# M640X.net
KiCad netlist of a schematic drawn in EAGLE
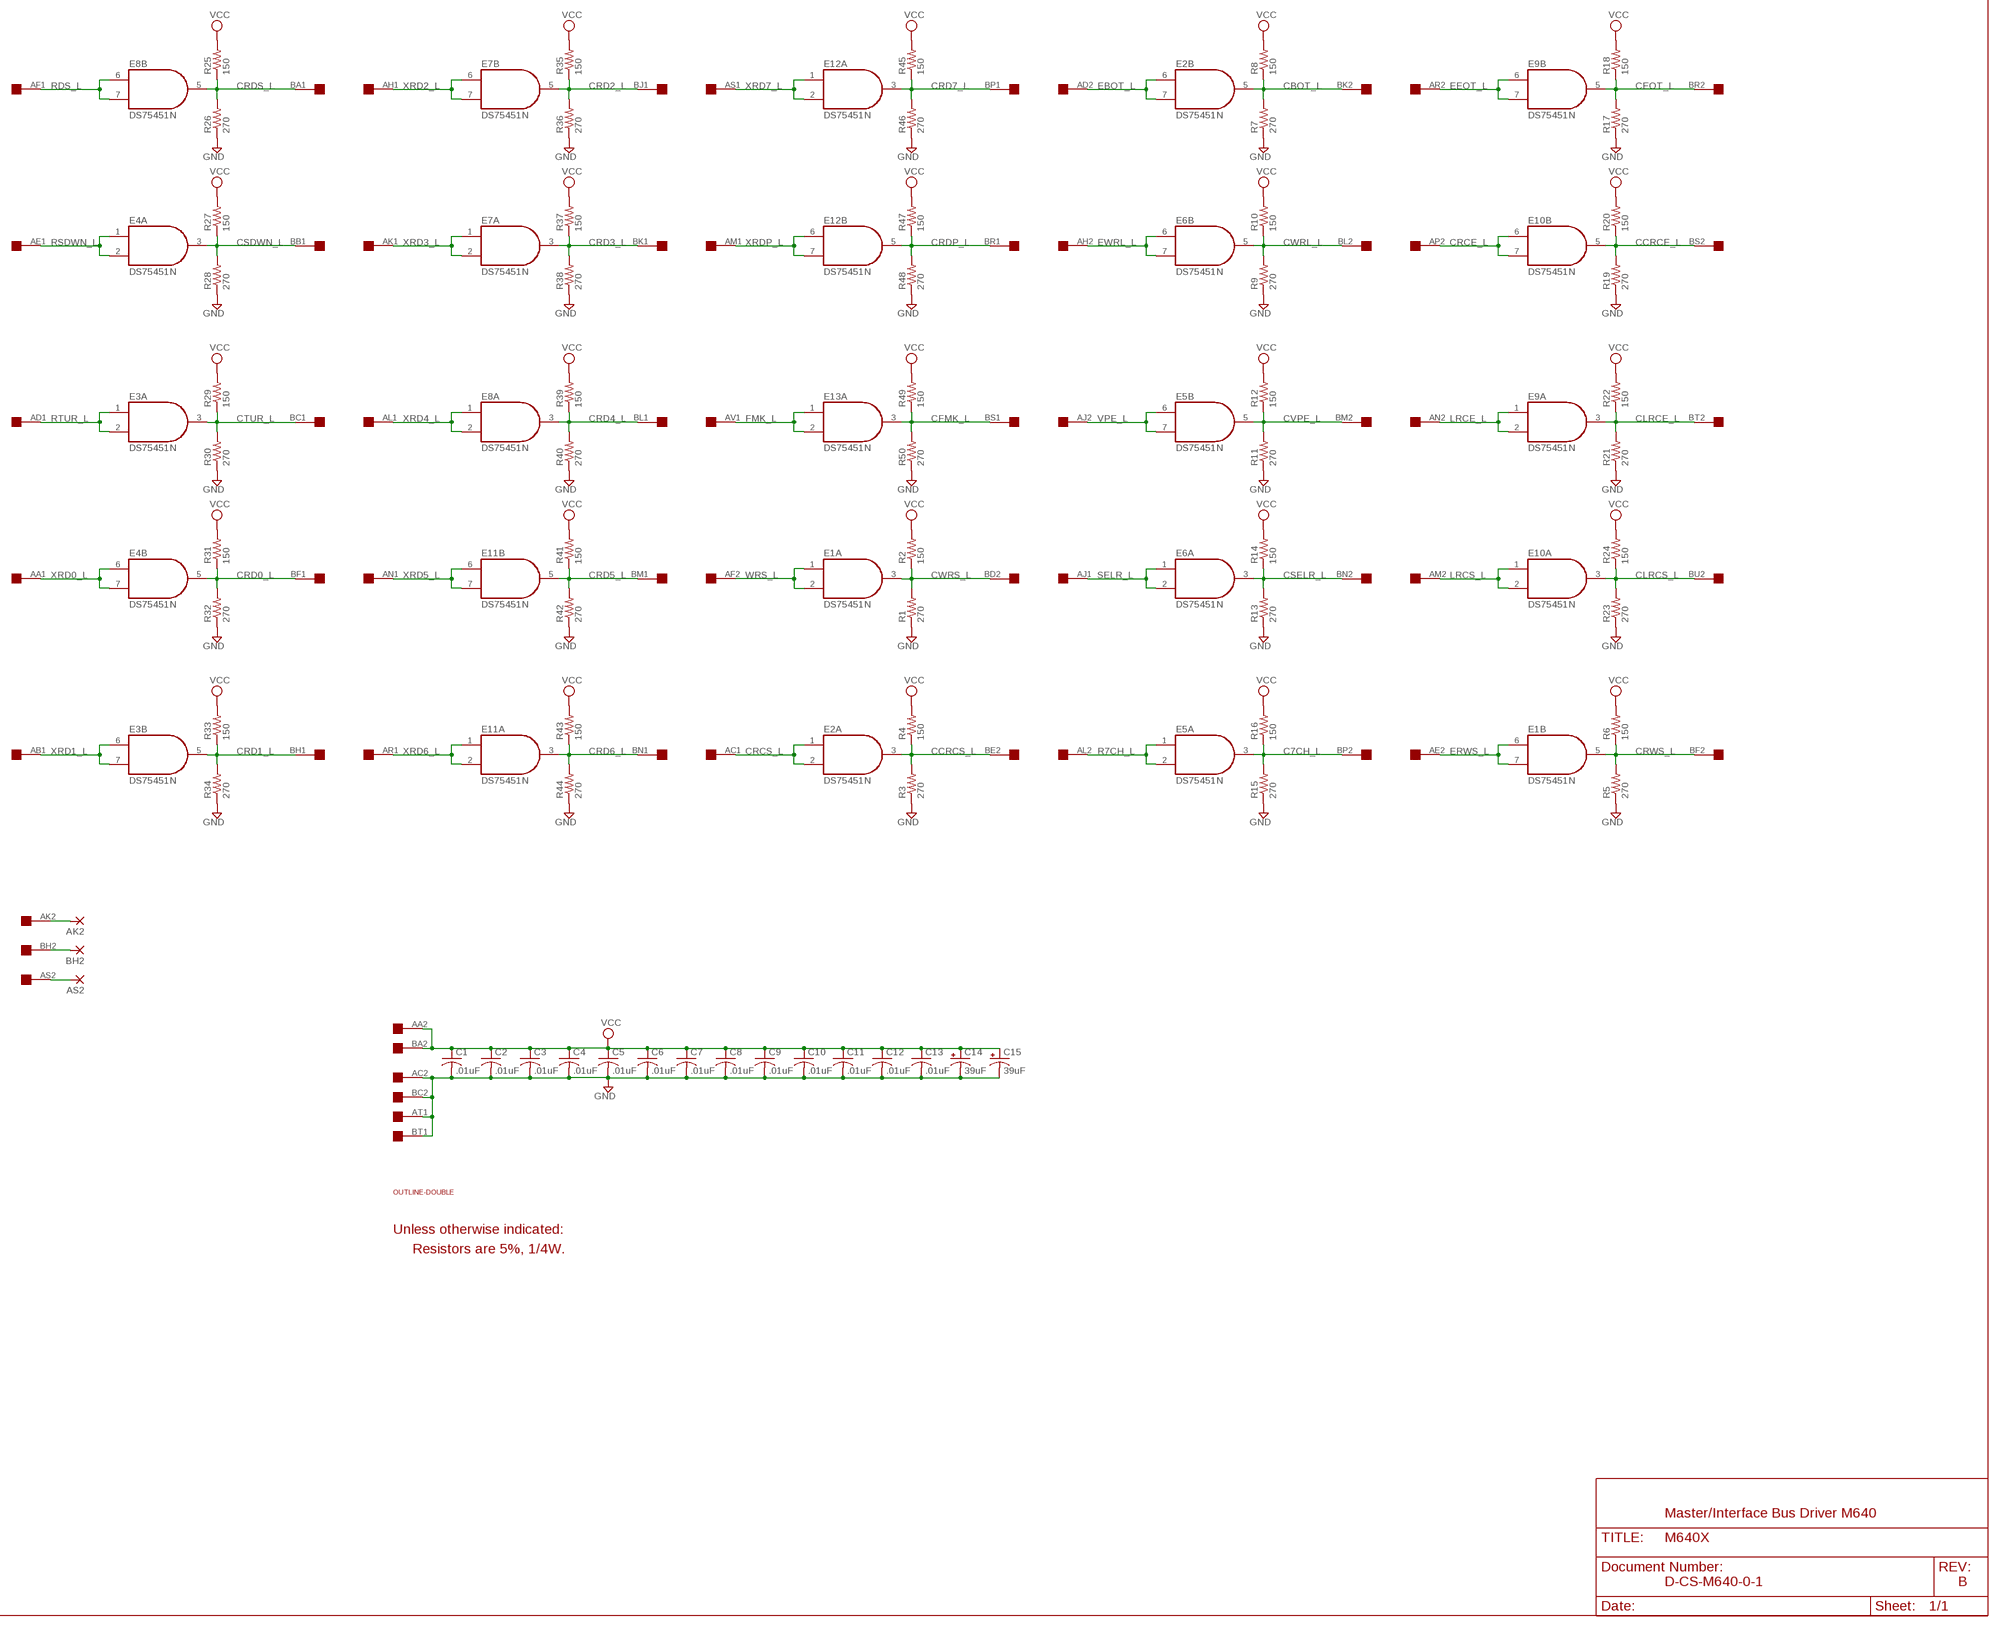
[diagram p0: schematic, sheet 1]

(export (version "E")
  (design (tool "Eeschema 10.0.6"))
  (components
    (comp (ref "AK2")
      (value "1,6/0,8")
      (footprint "eagle-import:1,6_0,8")
      (libsource (lib "eagle-import") (part "1,6/0,8"))
    )
    (comp (ref "AS2")
      (value "1,6/0,8")
      (footprint "eagle-import:1,6_0,8")
      (libsource (lib "eagle-import") (part "1,6/0,8"))
    )
    (comp (ref "BH2")
      (value "1,6/0,8")
      (footprint "eagle-import:1,6_0,8")
      (libsource (lib "eagle-import") (part "1,6/0,8"))
    )
    (comp (ref "C1")
      (value ".01uF")
      (footprint "eagle-import:C050-025X075")
      (libsource (lib "eagle-import") (part "C-US050-025X075"))
    )
    (comp (ref "C2")
      (value ".01uF")
      (footprint "eagle-import:C050-025X075")
      (libsource (lib "eagle-import") (part "C-US050-025X075"))
    )
    (comp (ref "C3")
      (value ".01uF")
      (footprint "eagle-import:C050-025X075")
      (libsource (lib "eagle-import") (part "C-US050-025X075"))
    )
    (comp (ref "C4")
      (value ".01uF")
      (footprint "eagle-import:C050-025X075")
      (libsource (lib "eagle-import") (part "C-US050-025X075"))
    )
    (comp (ref "C5")
      (value ".01uF")
      (footprint "eagle-import:C050-025X075")
      (libsource (lib "eagle-import") (part "C-US050-025X075"))
    )
    (comp (ref "C6")
      (value ".01uF")
      (footprint "eagle-import:C050-025X075")
      (libsource (lib "eagle-import") (part "C-US050-025X075"))
    )
    (comp (ref "C7")
      (value ".01uF")
      (footprint "eagle-import:C050-025X075")
      (libsource (lib "eagle-import") (part "C-US050-025X075"))
    )
    (comp (ref "C8")
      (value ".01uF")
      (footprint "eagle-import:C050-025X075")
      (libsource (lib "eagle-import") (part "C-US050-025X075"))
    )
    (comp (ref "C9")
      (value ".01uF")
      (footprint "eagle-import:C050-025X075")
      (libsource (lib "eagle-import") (part "C-US050-025X075"))
    )
    (comp (ref "C10")
      (value ".01uF")
      (footprint "eagle-import:C050-025X075")
      (libsource (lib "eagle-import") (part "C-US050-025X075"))
    )
    (comp (ref "C11")
      (value ".01uF")
      (footprint "eagle-import:C050-025X075")
      (libsource (lib "eagle-import") (part "C-US050-025X075"))
    )
    (comp (ref "C12")
      (value ".01uF")
      (footprint "eagle-import:C050-025X075")
      (libsource (lib "eagle-import") (part "C-US050-025X075"))
    )
    (comp (ref "C13")
      (value ".01uF")
      (footprint "eagle-import:C050-025X075")
      (libsource (lib "eagle-import") (part "C-US050-025X075"))
    )
    (comp (ref "C14")
      (value "39uF")
      (footprint "eagle-import:E12-8")
      (libsource (lib "eagle-import") (part "CPOL-USE20-8AXIAL"))
    )
    (comp (ref "C15")
      (value "39uF")
      (footprint "eagle-import:E12-8")
      (libsource (lib "eagle-import") (part "CPOL-USE20-8AXIAL"))
    )
    (comp (ref "E1")
      (value "DS75451N")
      (footprint "eagle-import:DIL08")
      (libsource (lib "eagle-import") (part "DS75451N"))
    )
    (comp (ref "E2")
      (value "DS75451N")
      (footprint "eagle-import:DIL08")
      (libsource (lib "eagle-import") (part "DS75451N"))
    )
    (comp (ref "E3")
      (value "DS75451N")
      (footprint "eagle-import:DIL08")
      (libsource (lib "eagle-import") (part "DS75451N"))
    )
    (comp (ref "E4")
      (value "DS75451N")
      (footprint "eagle-import:DIL08")
      (libsource (lib "eagle-import") (part "DS75451N"))
    )
    (comp (ref "E5")
      (value "DS75451N")
      (footprint "eagle-import:DIL08")
      (libsource (lib "eagle-import") (part "DS75451N"))
    )
    (comp (ref "E6")
      (value "DS75451N")
      (footprint "eagle-import:DIL08")
      (libsource (lib "eagle-import") (part "DS75451N"))
    )
    (comp (ref "E7")
      (value "DS75451N")
      (footprint "eagle-import:DIL08")
      (libsource (lib "eagle-import") (part "DS75451N"))
    )
    (comp (ref "E8")
      (value "DS75451N")
      (footprint "eagle-import:DIL08")
      (libsource (lib "eagle-import") (part "DS75451N"))
    )
    (comp (ref "E9")
      (value "DS75451N")
      (footprint "eagle-import:DIL08")
      (libsource (lib "eagle-import") (part "DS75451N"))
    )
    (comp (ref "E10")
      (value "DS75451N")
      (footprint "eagle-import:DIL08")
      (libsource (lib "eagle-import") (part "DS75451N"))
    )
    (comp (ref "E11")
      (value "DS75451N")
      (footprint "eagle-import:DIL08")
      (libsource (lib "eagle-import") (part "DS75451N"))
    )
    (comp (ref "E12")
      (value "DS75451N")
      (footprint "eagle-import:DIL08")
      (libsource (lib "eagle-import") (part "DS75451N"))
    )
    (comp (ref "E13")
      (value "DS75451N")
      (footprint "eagle-import:DIL08")
      (libsource (lib "eagle-import") (part "DS75451N"))
    )
    (comp (ref "R1")
      (value "270")
      (footprint "eagle-import:0207_10")
      (libsource (lib "eagle-import") (part "R-US_0207/10"))
    )
    (comp (ref "R2")
      (value "150")
      (footprint "eagle-import:0207_10")
      (libsource (lib "eagle-import") (part "R-US_0207/10"))
    )
    (comp (ref "R3")
      (value "270")
      (footprint "eagle-import:0207_10")
      (libsource (lib "eagle-import") (part "R-US_0207/10"))
    )
    (comp (ref "R4")
      (value "150")
      (footprint "eagle-import:0207_10")
      (libsource (lib "eagle-import") (part "R-US_0207/10"))
    )
    (comp (ref "R5")
      (value "270")
      (footprint "eagle-import:0207_10")
      (libsource (lib "eagle-import") (part "R-US_0207/10"))
    )
    (comp (ref "R6")
      (value "150")
      (footprint "eagle-import:0207_10")
      (libsource (lib "eagle-import") (part "R-US_0207/10"))
    )
    (comp (ref "R7")
      (value "270")
      (footprint "eagle-import:0207_10")
      (libsource (lib "eagle-import") (part "R-US_0207/10"))
    )
    (comp (ref "R8")
      (value "150")
      (footprint "eagle-import:0207_10")
      (libsource (lib "eagle-import") (part "R-US_0207/10"))
    )
    (comp (ref "R9")
      (value "270")
      (footprint "eagle-import:0207_10")
      (libsource (lib "eagle-import") (part "R-US_0207/10"))
    )
    (comp (ref "R10")
      (value "150")
      (footprint "eagle-import:0207_10")
      (libsource (lib "eagle-import") (part "R-US_0207/10"))
    )
    (comp (ref "R11")
      (value "270")
      (footprint "eagle-import:0207_10")
      (libsource (lib "eagle-import") (part "R-US_0207/10"))
    )
    (comp (ref "R12")
      (value "150")
      (footprint "eagle-import:0207_10")
      (libsource (lib "eagle-import") (part "R-US_0207/10"))
    )
    (comp (ref "R13")
      (value "270")
      (footprint "eagle-import:0207_10")
      (libsource (lib "eagle-import") (part "R-US_0207/10"))
    )
    (comp (ref "R14")
      (value "150")
      (footprint "eagle-import:0207_10")
      (libsource (lib "eagle-import") (part "R-US_0207/10"))
    )
    (comp (ref "R15")
      (value "270")
      (footprint "eagle-import:0207_10")
      (libsource (lib "eagle-import") (part "R-US_0207/10"))
    )
    (comp (ref "R16")
      (value "150")
      (footprint "eagle-import:0207_10")
      (libsource (lib "eagle-import") (part "R-US_0207/10"))
    )
    (comp (ref "R17")
      (value "270")
      (footprint "eagle-import:0207_10")
      (libsource (lib "eagle-import") (part "R-US_0207/10"))
    )
    (comp (ref "R18")
      (value "150")
      (footprint "eagle-import:0207_10")
      (libsource (lib "eagle-import") (part "R-US_0207/10"))
    )
    (comp (ref "R19")
      (value "270")
      (footprint "eagle-import:0207_10")
      (libsource (lib "eagle-import") (part "R-US_0207/10"))
    )
    (comp (ref "R20")
      (value "150")
      (footprint "eagle-import:0207_10")
      (libsource (lib "eagle-import") (part "R-US_0207/10"))
    )
    (comp (ref "R21")
      (value "270")
      (footprint "eagle-import:0207_10")
      (libsource (lib "eagle-import") (part "R-US_0207/10"))
    )
    (comp (ref "R22")
      (value "150")
      (footprint "eagle-import:0207_10")
      (libsource (lib "eagle-import") (part "R-US_0207/10"))
    )
    (comp (ref "R23")
      (value "270")
      (footprint "eagle-import:0207_10")
      (libsource (lib "eagle-import") (part "R-US_0207/10"))
    )
    (comp (ref "R24")
      (value "150")
      (footprint "eagle-import:0207_10")
      (libsource (lib "eagle-import") (part "R-US_0207/10"))
    )
    (comp (ref "R25")
      (value "150")
      (footprint "eagle-import:0207_10")
      (libsource (lib "eagle-import") (part "R-US_0207/10"))
    )
    (comp (ref "R26")
      (value "270")
      (footprint "eagle-import:0207_10")
      (libsource (lib "eagle-import") (part "R-US_0207/10"))
    )
    (comp (ref "R27")
      (value "150")
      (footprint "eagle-import:0207_10")
      (libsource (lib "eagle-import") (part "R-US_0207/10"))
    )
    (comp (ref "R28")
      (value "270")
      (footprint "eagle-import:0207_10")
      (libsource (lib "eagle-import") (part "R-US_0207/10"))
    )
    (comp (ref "R29")
      (value "150")
      (footprint "eagle-import:0207_10")
      (libsource (lib "eagle-import") (part "R-US_0207/10"))
    )
    (comp (ref "R30")
      (value "270")
      (footprint "eagle-import:0207_10")
      (libsource (lib "eagle-import") (part "R-US_0207/10"))
    )
    (comp (ref "R31")
      (value "150")
      (footprint "eagle-import:0207_10")
      (libsource (lib "eagle-import") (part "R-US_0207/10"))
    )
    (comp (ref "R32")
      (value "270")
      (footprint "eagle-import:0207_10")
      (libsource (lib "eagle-import") (part "R-US_0207/10"))
    )
    (comp (ref "R33")
      (value "150")
      (footprint "eagle-import:0207_10")
      (libsource (lib "eagle-import") (part "R-US_0207/10"))
    )
    (comp (ref "R34")
      (value "270")
      (footprint "eagle-import:0207_10")
      (libsource (lib "eagle-import") (part "R-US_0207/10"))
    )
    (comp (ref "R35")
      (value "150")
      (footprint "eagle-import:0207_10")
      (libsource (lib "eagle-import") (part "R-US_0207/10"))
    )
    (comp (ref "R36")
      (value "270")
      (footprint "eagle-import:0207_10")
      (libsource (lib "eagle-import") (part "R-US_0207/10"))
    )
    (comp (ref "R37")
      (value "150")
      (footprint "eagle-import:0207_10")
      (libsource (lib "eagle-import") (part "R-US_0207/10"))
    )
    (comp (ref "R38")
      (value "270")
      (footprint "eagle-import:0207_10")
      (libsource (lib "eagle-import") (part "R-US_0207/10"))
    )
    (comp (ref "R39")
      (value "150")
      (footprint "eagle-import:0207_10")
      (libsource (lib "eagle-import") (part "R-US_0207/10"))
    )
    (comp (ref "R40")
      (value "270")
      (footprint "eagle-import:0207_10")
      (libsource (lib "eagle-import") (part "R-US_0207/10"))
    )
    (comp (ref "R41")
      (value "150")
      (footprint "eagle-import:0207_10")
      (libsource (lib "eagle-import") (part "R-US_0207/10"))
    )
    (comp (ref "R42")
      (value "270")
      (footprint "eagle-import:0207_10")
      (libsource (lib "eagle-import") (part "R-US_0207/10"))
    )
    (comp (ref "R43")
      (value "150")
      (footprint "eagle-import:0207_10")
      (libsource (lib "eagle-import") (part "R-US_0207/10"))
    )
    (comp (ref "R44")
      (value "270")
      (footprint "eagle-import:0207_10")
      (libsource (lib "eagle-import") (part "R-US_0207/10"))
    )
    (comp (ref "R45")
      (value "150")
      (footprint "eagle-import:0207_10")
      (libsource (lib "eagle-import") (part "R-US_0207/10"))
    )
    (comp (ref "R46")
      (value "270")
      (footprint "eagle-import:0207_10")
      (libsource (lib "eagle-import") (part "R-US_0207/10"))
    )
    (comp (ref "R47")
      (value "150")
      (footprint "eagle-import:0207_10")
      (libsource (lib "eagle-import") (part "R-US_0207/10"))
    )
    (comp (ref "R48")
      (value "270")
      (footprint "eagle-import:0207_10")
      (libsource (lib "eagle-import") (part "R-US_0207/10"))
    )
    (comp (ref "R49")
      (value "150")
      (footprint "eagle-import:0207_10")
      (libsource (lib "eagle-import") (part "R-US_0207/10"))
    )
    (comp (ref "R50")
      (value "270")
      (footprint "eagle-import:0207_10")
      (libsource (lib "eagle-import") (part "R-US_0207/10"))
    )
    (comp (ref "U$1")
      (value "DOUBLE")
      (footprint "eagle-import:EDGE-CON4")
      (libsource (lib "eagle-import") (part "DOUBLE"))
    )
    (comp (ref "U$2")
      (value "OUTLINE-DOUBLE")
      (footprint "eagle-import:DOUBLE")
      (libsource (lib "eagle-import") (part "OUTLINE-DOUBLE"))
    )
  )
  (nets
    (net (code "1") (name "/C7CH_L") (class "Default")
      (node (ref "E5") (pin "3") (pinfunction "O_3") (pintype "open_collector"))
      (node (ref "R15") (pin "2") (pinfunction "2_2") (pintype "passive"))
      (node (ref "R16") (pin "1") (pinfunction "1_1") (pintype "passive"))
      (node (ref "U$1") (pin "BP2") (pinfunction "1_BP2") (pintype "bidirectional"))
    )
    (net (code "2") (name "/CBOT_L") (class "Default")
      (node (ref "E2") (pin "5") (pinfunction "O_5") (pintype "open_collector"))
      (node (ref "R7") (pin "2") (pinfunction "2_2") (pintype "passive"))
      (node (ref "R8") (pin "1") (pinfunction "1_1") (pintype "passive"))
      (node (ref "U$1") (pin "BK2") (pinfunction "1_BK2") (pintype "bidirectional"))
    )
    (net (code "3") (name "/CCRCE_L") (class "Default")
      (node (ref "E10") (pin "5") (pinfunction "O_5") (pintype "open_collector"))
      (node (ref "R19") (pin "2") (pinfunction "2_2") (pintype "passive"))
      (node (ref "R20") (pin "1") (pinfunction "1_1") (pintype "passive"))
      (node (ref "U$1") (pin "BS2") (pinfunction "1_BS2") (pintype "bidirectional"))
    )
    (net (code "4") (name "/CCRCS_L") (class "Default")
      (node (ref "E2") (pin "3") (pinfunction "O_3") (pintype "open_collector"))
      (node (ref "R3") (pin "2") (pinfunction "2_2") (pintype "passive"))
      (node (ref "R4") (pin "1") (pinfunction "1_1") (pintype "passive"))
      (node (ref "U$1") (pin "BE2") (pinfunction "1_BE2") (pintype "bidirectional"))
    )
    (net (code "5") (name "/CEOT_L") (class "Default")
      (node (ref "E9") (pin "5") (pinfunction "O_5") (pintype "open_collector"))
      (node (ref "R17") (pin "2") (pinfunction "2_2") (pintype "passive"))
      (node (ref "R18") (pin "1") (pinfunction "1_1") (pintype "passive"))
      (node (ref "U$1") (pin "BR2") (pinfunction "1_BR2") (pintype "bidirectional"))
    )
    (net (code "6") (name "/CFMK_L") (class "Default")
      (node (ref "E13") (pin "3") (pinfunction "O_3") (pintype "open_collector"))
      (node (ref "R49") (pin "1") (pinfunction "1_1") (pintype "passive"))
      (node (ref "R50") (pin "2") (pinfunction "2_2") (pintype "passive"))
      (node (ref "U$1") (pin "BS1") (pinfunction "1_BS1") (pintype "bidirectional"))
    )
    (net (code "7") (name "/CLRCE_L") (class "Default")
      (node (ref "E9") (pin "3") (pinfunction "O_3") (pintype "open_collector"))
      (node (ref "R21") (pin "2") (pinfunction "2_2") (pintype "passive"))
      (node (ref "R22") (pin "1") (pinfunction "1_1") (pintype "passive"))
      (node (ref "U$1") (pin "BT2") (pinfunction "1_BT2") (pintype "bidirectional"))
    )
    (net (code "8") (name "/CLRCS_L") (class "Default")
      (node (ref "E10") (pin "3") (pinfunction "O_3") (pintype "open_collector"))
      (node (ref "R23") (pin "2") (pinfunction "2_2") (pintype "passive"))
      (node (ref "R24") (pin "1") (pinfunction "1_1") (pintype "passive"))
      (node (ref "U$1") (pin "BU2") (pinfunction "1_BU2") (pintype "bidirectional"))
    )
    (net (code "9") (name "/CRCE_L") (class "Default")
      (node (ref "E10") (pin "6") (pinfunction "I0_6") (pintype "input"))
      (node (ref "E10") (pin "7") (pinfunction "I1_7") (pintype "input"))
      (node (ref "U$1") (pin "AP2") (pinfunction "1_AP2") (pintype "bidirectional"))
    )
    (net (code "10") (name "/CRCS_L") (class "Default")
      (node (ref "E2") (pin "1") (pinfunction "I0_1") (pintype "input"))
      (node (ref "E2") (pin "2") (pinfunction "I1_2") (pintype "input"))
      (node (ref "U$1") (pin "AC1") (pinfunction "1_AC1") (pintype "bidirectional"))
    )
    (net (code "11") (name "/CRD0_L") (class "Default")
      (node (ref "E4") (pin "5") (pinfunction "O_5") (pintype "open_collector"))
      (node (ref "R31") (pin "1") (pinfunction "1_1") (pintype "passive"))
      (node (ref "R32") (pin "2") (pinfunction "2_2") (pintype "passive"))
      (node (ref "U$1") (pin "BF1") (pinfunction "1_BF1") (pintype "bidirectional"))
    )
    (net (code "12") (name "/CRD1_L") (class "Default")
      (node (ref "E3") (pin "5") (pinfunction "O_5") (pintype "open_collector"))
      (node (ref "R33") (pin "1") (pinfunction "1_1") (pintype "passive"))
      (node (ref "R34") (pin "2") (pinfunction "2_2") (pintype "passive"))
      (node (ref "U$1") (pin "BH1") (pinfunction "1_BH1") (pintype "bidirectional"))
    )
    (net (code "13") (name "/CRD2_L") (class "Default")
      (node (ref "E7") (pin "5") (pinfunction "O_5") (pintype "open_collector"))
      (node (ref "R35") (pin "1") (pinfunction "1_1") (pintype "passive"))
      (node (ref "R36") (pin "2") (pinfunction "2_2") (pintype "passive"))
      (node (ref "U$1") (pin "BJ1") (pinfunction "1_BJ1") (pintype "bidirectional"))
    )
    (net (code "14") (name "/CRD3_L") (class "Default")
      (node (ref "E7") (pin "3") (pinfunction "O_3") (pintype "open_collector"))
      (node (ref "R37") (pin "1") (pinfunction "1_1") (pintype "passive"))
      (node (ref "R38") (pin "2") (pinfunction "2_2") (pintype "passive"))
      (node (ref "U$1") (pin "BK1") (pinfunction "1_BK1") (pintype "bidirectional"))
    )
    (net (code "15") (name "/CRD4_L") (class "Default")
      (node (ref "E8") (pin "3") (pinfunction "O_3") (pintype "open_collector"))
      (node (ref "R39") (pin "1") (pinfunction "1_1") (pintype "passive"))
      (node (ref "R40") (pin "2") (pinfunction "2_2") (pintype "passive"))
      (node (ref "U$1") (pin "BL1") (pinfunction "1_BL1") (pintype "bidirectional"))
    )
    (net (code "16") (name "/CRD5_L") (class "Default")
      (node (ref "E11") (pin "5") (pinfunction "O_5") (pintype "open_collector"))
      (node (ref "R41") (pin "1") (pinfunction "1_1") (pintype "passive"))
      (node (ref "R42") (pin "2") (pinfunction "2_2") (pintype "passive"))
      (node (ref "U$1") (pin "BM1") (pinfunction "1_BM1") (pintype "bidirectional"))
    )
    (net (code "17") (name "/CRD6_L") (class "Default")
      (node (ref "E11") (pin "3") (pinfunction "O_3") (pintype "open_collector"))
      (node (ref "R43") (pin "1") (pinfunction "1_1") (pintype "passive"))
      (node (ref "R44") (pin "2") (pinfunction "2_2") (pintype "passive"))
      (node (ref "U$1") (pin "BN1") (pinfunction "1_BN1") (pintype "bidirectional"))
    )
    (net (code "18") (name "/CRD7_L") (class "Default")
      (node (ref "E12") (pin "3") (pinfunction "O_3") (pintype "open_collector"))
      (node (ref "R45") (pin "1") (pinfunction "1_1") (pintype "passive"))
      (node (ref "R46") (pin "2") (pinfunction "2_2") (pintype "passive"))
      (node (ref "U$1") (pin "BP1") (pinfunction "1_BP1") (pintype "bidirectional"))
    )
    (net (code "19") (name "/CRDP_L") (class "Default")
      (node (ref "E12") (pin "5") (pinfunction "O_5") (pintype "open_collector"))
      (node (ref "R47") (pin "1") (pinfunction "1_1") (pintype "passive"))
      (node (ref "R48") (pin "2") (pinfunction "2_2") (pintype "passive"))
      (node (ref "U$1") (pin "BR1") (pinfunction "1_BR1") (pintype "bidirectional"))
    )
    (net (code "20") (name "/CRDS_L") (class "Default")
      (node (ref "E8") (pin "5") (pinfunction "O_5") (pintype "open_collector"))
      (node (ref "R25") (pin "1") (pinfunction "1_1") (pintype "passive"))
      (node (ref "R26") (pin "2") (pinfunction "2_2") (pintype "passive"))
      (node (ref "U$1") (pin "BA1") (pinfunction "1_BA1") (pintype "bidirectional"))
    )
    (net (code "21") (name "/CRWS_L") (class "Default")
      (node (ref "E1") (pin "5") (pinfunction "O_5") (pintype "open_collector"))
      (node (ref "R5") (pin "2") (pinfunction "2_2") (pintype "passive"))
      (node (ref "R6") (pin "1") (pinfunction "1_1") (pintype "passive"))
      (node (ref "U$1") (pin "BF2") (pinfunction "1_BF2") (pintype "bidirectional"))
    )
    (net (code "22") (name "/CSDWN_L") (class "Default")
      (node (ref "E4") (pin "3") (pinfunction "O_3") (pintype "open_collector"))
      (node (ref "R27") (pin "1") (pinfunction "1_1") (pintype "passive"))
      (node (ref "R28") (pin "2") (pinfunction "2_2") (pintype "passive"))
      (node (ref "U$1") (pin "BB1") (pinfunction "1_BB1") (pintype "bidirectional"))
    )
    (net (code "23") (name "/CSELR_L") (class "Default")
      (node (ref "E6") (pin "3") (pinfunction "O_3") (pintype "open_collector"))
      (node (ref "R13") (pin "2") (pinfunction "2_2") (pintype "passive"))
      (node (ref "R14") (pin "1") (pinfunction "1_1") (pintype "passive"))
      (node (ref "U$1") (pin "BN2") (pinfunction "1_BN2") (pintype "bidirectional"))
    )
    (net (code "24") (name "/CTUR_L") (class "Default")
      (node (ref "E3") (pin "3") (pinfunction "O_3") (pintype "open_collector"))
      (node (ref "R29") (pin "1") (pinfunction "1_1") (pintype "passive"))
      (node (ref "R30") (pin "2") (pinfunction "2_2") (pintype "passive"))
      (node (ref "U$1") (pin "BC1") (pinfunction "1_BC1") (pintype "bidirectional"))
    )
    (net (code "25") (name "/CVPE_L") (class "Default")
      (node (ref "E5") (pin "5") (pinfunction "O_5") (pintype "open_collector"))
      (node (ref "R11") (pin "2") (pinfunction "2_2") (pintype "passive"))
      (node (ref "R12") (pin "1") (pinfunction "1_1") (pintype "passive"))
      (node (ref "U$1") (pin "BM2") (pinfunction "1_BM2") (pintype "bidirectional"))
    )
    (net (code "26") (name "/CWRL_L") (class "Default")
      (node (ref "E6") (pin "5") (pinfunction "O_5") (pintype "open_collector"))
      (node (ref "R10") (pin "1") (pinfunction "1_1") (pintype "passive"))
      (node (ref "R9") (pin "2") (pinfunction "2_2") (pintype "passive"))
      (node (ref "U$1") (pin "BL2") (pinfunction "1_BL2") (pintype "bidirectional"))
    )
    (net (code "27") (name "/CWRS_L") (class "Default")
      (node (ref "E1") (pin "3") (pinfunction "O_3") (pintype "open_collector"))
      (node (ref "R1") (pin "2") (pinfunction "2_2") (pintype "passive"))
      (node (ref "R2") (pin "1") (pinfunction "1_1") (pintype "passive"))
      (node (ref "U$1") (pin "BD2") (pinfunction "1_BD2") (pintype "bidirectional"))
    )
    (net (code "28") (name "/EBOT_L") (class "Default")
      (node (ref "E2") (pin "6") (pinfunction "I0_6") (pintype "input"))
      (node (ref "E2") (pin "7") (pinfunction "I1_7") (pintype "input"))
      (node (ref "U$1") (pin "AD2") (pinfunction "1_AD2") (pintype "bidirectional"))
    )
    (net (code "29") (name "/EEOT_L") (class "Default")
      (node (ref "E9") (pin "6") (pinfunction "I0_6") (pintype "input"))
      (node (ref "E9") (pin "7") (pinfunction "I1_7") (pintype "input"))
      (node (ref "U$1") (pin "AR2") (pinfunction "1_AR2") (pintype "bidirectional"))
    )
    (net (code "30") (name "/ERWS_L") (class "Default")
      (node (ref "E1") (pin "6") (pinfunction "I0_6") (pintype "input"))
      (node (ref "E1") (pin "7") (pinfunction "I1_7") (pintype "input"))
      (node (ref "U$1") (pin "AE2") (pinfunction "1_AE2") (pintype "bidirectional"))
    )
    (net (code "31") (name "/EWRL_L") (class "Default")
      (node (ref "E6") (pin "6") (pinfunction "I0_6") (pintype "input"))
      (node (ref "E6") (pin "7") (pinfunction "I1_7") (pintype "input"))
      (node (ref "U$1") (pin "AH2") (pinfunction "1_AH2") (pintype "bidirectional"))
    )
    (net (code "32") (name "/FMK_L") (class "Default")
      (node (ref "E13") (pin "1") (pinfunction "I0_1") (pintype "input"))
      (node (ref "E13") (pin "2") (pinfunction "I1_2") (pintype "input"))
      (node (ref "U$1") (pin "AV1") (pinfunction "1_AV1") (pintype "bidirectional"))
    )
    (net (code "33") (name "/LRCE_L") (class "Default")
      (node (ref "E9") (pin "1") (pinfunction "I0_1") (pintype "input"))
      (node (ref "E9") (pin "2") (pinfunction "I1_2") (pintype "input"))
      (node (ref "U$1") (pin "AN2") (pinfunction "1_AN2") (pintype "bidirectional"))
    )
    (net (code "34") (name "/LRCS_L") (class "Default")
      (node (ref "E10") (pin "1") (pinfunction "I0_1") (pintype "input"))
      (node (ref "E10") (pin "2") (pinfunction "I1_2") (pintype "input"))
      (node (ref "U$1") (pin "AM2") (pinfunction "1_AM2") (pintype "bidirectional"))
    )
    (net (code "35") (name "/R7CH_L") (class "Default")
      (node (ref "E5") (pin "1") (pinfunction "I0_1") (pintype "input"))
      (node (ref "E5") (pin "2") (pinfunction "I1_2") (pintype "input"))
      (node (ref "U$1") (pin "AL2") (pinfunction "1_AL2") (pintype "bidirectional"))
    )
    (net (code "36") (name "/RDS_L") (class "Default")
      (node (ref "E8") (pin "6") (pinfunction "I0_6") (pintype "input"))
      (node (ref "E8") (pin "7") (pinfunction "I1_7") (pintype "input"))
      (node (ref "U$1") (pin "AF1") (pinfunction "1_AF1") (pintype "bidirectional"))
    )
    (net (code "37") (name "/RSDWN_L") (class "Default")
      (node (ref "E4") (pin "1") (pinfunction "I0_1") (pintype "input"))
      (node (ref "E4") (pin "2") (pinfunction "I1_2") (pintype "input"))
      (node (ref "U$1") (pin "AE1") (pinfunction "1_AE1") (pintype "bidirectional"))
    )
    (net (code "38") (name "/RTUR_L") (class "Default")
      (node (ref "E3") (pin "1") (pinfunction "I0_1") (pintype "input"))
      (node (ref "E3") (pin "2") (pinfunction "I1_2") (pintype "input"))
      (node (ref "U$1") (pin "AD1") (pinfunction "1_AD1") (pintype "bidirectional"))
    )
    (net (code "39") (name "/SELR_L") (class "Default")
      (node (ref "E6") (pin "1") (pinfunction "I0_1") (pintype "input"))
      (node (ref "E6") (pin "2") (pinfunction "I1_2") (pintype "input"))
      (node (ref "U$1") (pin "AJ1") (pinfunction "1_AJ1") (pintype "bidirectional"))
    )
    (net (code "40") (name "/VPE_L") (class "Default")
      (node (ref "E5") (pin "6") (pinfunction "I0_6") (pintype "input"))
      (node (ref "E5") (pin "7") (pinfunction "I1_7") (pintype "input"))
      (node (ref "U$1") (pin "AJ2") (pinfunction "1_AJ2") (pintype "bidirectional"))
    )
    (net (code "41") (name "/WRS_L") (class "Default")
      (node (ref "E1") (pin "1") (pinfunction "I0_1") (pintype "input"))
      (node (ref "E1") (pin "2") (pinfunction "I1_2") (pintype "input"))
      (node (ref "U$1") (pin "AF2") (pinfunction "1_AF2") (pintype "bidirectional"))
    )
    (net (code "42") (name "/XRD0_L") (class "Default")
      (node (ref "E4") (pin "6") (pinfunction "I0_6") (pintype "input"))
      (node (ref "E4") (pin "7") (pinfunction "I1_7") (pintype "input"))
      (node (ref "U$1") (pin "AA1") (pinfunction "1_AA1") (pintype "bidirectional"))
    )
    (net (code "43") (name "/XRD1_L") (class "Default")
      (node (ref "E3") (pin "6") (pinfunction "I0_6") (pintype "input"))
      (node (ref "E3") (pin "7") (pinfunction "I1_7") (pintype "input"))
      (node (ref "U$1") (pin "AB1") (pinfunction "1_AB1") (pintype "bidirectional"))
    )
    (net (code "44") (name "/XRD2_L") (class "Default")
      (node (ref "E7") (pin "6") (pinfunction "I0_6") (pintype "input"))
      (node (ref "E7") (pin "7") (pinfunction "I1_7") (pintype "input"))
      (node (ref "U$1") (pin "AH1") (pinfunction "1_AH1") (pintype "bidirectional"))
    )
    (net (code "45") (name "/XRD3_L") (class "Default")
      (node (ref "E7") (pin "1") (pinfunction "I0_1") (pintype "input"))
      (node (ref "E7") (pin "2") (pinfunction "I1_2") (pintype "input"))
      (node (ref "U$1") (pin "AK1") (pinfunction "1_AK1") (pintype "bidirectional"))
    )
    (net (code "46") (name "/XRD4_L") (class "Default")
      (node (ref "E8") (pin "1") (pinfunction "I0_1") (pintype "input"))
      (node (ref "E8") (pin "2") (pinfunction "I1_2") (pintype "input"))
      (node (ref "U$1") (pin "AL1") (pinfunction "1_AL1") (pintype "bidirectional"))
    )
    (net (code "47") (name "/XRD5_L") (class "Default")
      (node (ref "E11") (pin "6") (pinfunction "I0_6") (pintype "input"))
      (node (ref "E11") (pin "7") (pinfunction "I1_7") (pintype "input"))
      (node (ref "U$1") (pin "AN1") (pinfunction "1_AN1") (pintype "bidirectional"))
    )
    (net (code "48") (name "/XRD6_L") (class "Default")
      (node (ref "E11") (pin "1") (pinfunction "I0_1") (pintype "input"))
      (node (ref "E11") (pin "2") (pinfunction "I1_2") (pintype "input"))
      (node (ref "U$1") (pin "AR1") (pinfunction "1_AR1") (pintype "bidirectional"))
    )
    (net (code "49") (name "/XRD7_L") (class "Default")
      (node (ref "E12") (pin "1") (pinfunction "I0_1") (pintype "input"))
      (node (ref "E12") (pin "2") (pinfunction "I1_2") (pintype "input"))
      (node (ref "U$1") (pin "AS1") (pinfunction "1_AS1") (pintype "bidirectional"))
    )
    (net (code "50") (name "/XRDP_L") (class "Default")
      (node (ref "E12") (pin "6") (pinfunction "I0_6") (pintype "input"))
      (node (ref "E12") (pin "7") (pinfunction "I1_7") (pintype "input"))
      (node (ref "U$1") (pin "AM1") (pinfunction "1_AM1") (pintype "bidirectional"))
    )
    (net (code "51") (name "GND") (class "Default")
      (node (ref "C1") (pin "2") (pinfunction "2_2") (pintype "passive"))
      (node (ref "C10") (pin "2") (pinfunction "2_2") (pintype "passive"))
      (node (ref "C11") (pin "2") (pinfunction "2_2") (pintype "passive"))
      (node (ref "C12") (pin "2") (pinfunction "2_2") (pintype "passive"))
      (node (ref "C13") (pin "2") (pinfunction "2_2") (pintype "passive"))
      (node (ref "C14") (pin "-") (pinfunction "-_-") (pintype "passive"))
      (node (ref "C15") (pin "-") (pinfunction "-_-") (pintype "passive"))
      (node (ref "C2") (pin "2") (pinfunction "2_2") (pintype "passive"))
      (node (ref "C3") (pin "2") (pinfunction "2_2") (pintype "passive"))
      (node (ref "C4") (pin "2") (pinfunction "2_2") (pintype "passive"))
      (node (ref "C5") (pin "2") (pinfunction "2_2") (pintype "passive"))
      (node (ref "C6") (pin "2") (pinfunction "2_2") (pintype "passive"))
      (node (ref "C7") (pin "2") (pinfunction "2_2") (pintype "passive"))
      (node (ref "C8") (pin "2") (pinfunction "2_2") (pintype "passive"))
      (node (ref "C9") (pin "2") (pinfunction "2_2") (pintype "passive"))
      (node (ref "R1") (pin "1") (pinfunction "1_1") (pintype "passive"))
      (node (ref "R11") (pin "1") (pinfunction "1_1") (pintype "passive"))
      (node (ref "R13") (pin "1") (pinfunction "1_1") (pintype "passive"))
      (node (ref "R15") (pin "1") (pinfunction "1_1") (pintype "passive"))
      (node (ref "R17") (pin "1") (pinfunction "1_1") (pintype "passive"))
      (node (ref "R19") (pin "1") (pinfunction "1_1") (pintype "passive"))
      (node (ref "R21") (pin "1") (pinfunction "1_1") (pintype "passive"))
      (node (ref "R23") (pin "1") (pinfunction "1_1") (pintype "passive"))
      (node (ref "R26") (pin "1") (pinfunction "1_1") (pintype "passive"))
      (node (ref "R28") (pin "1") (pinfunction "1_1") (pintype "passive"))
      (node (ref "R3") (pin "1") (pinfunction "1_1") (pintype "passive"))
      (node (ref "R30") (pin "1") (pinfunction "1_1") (pintype "passive"))
      (node (ref "R32") (pin "1") (pinfunction "1_1") (pintype "passive"))
      (node (ref "R34") (pin "1") (pinfunction "1_1") (pintype "passive"))
      (node (ref "R36") (pin "1") (pinfunction "1_1") (pintype "passive"))
      (node (ref "R38") (pin "1") (pinfunction "1_1") (pintype "passive"))
      (node (ref "R40") (pin "1") (pinfunction "1_1") (pintype "passive"))
      (node (ref "R42") (pin "1") (pinfunction "1_1") (pintype "passive"))
      (node (ref "R44") (pin "1") (pinfunction "1_1") (pintype "passive"))
      (node (ref "R46") (pin "1") (pinfunction "1_1") (pintype "passive"))
      (node (ref "R48") (pin "1") (pinfunction "1_1") (pintype "passive"))
      (node (ref "R5") (pin "1") (pinfunction "1_1") (pintype "passive"))
      (node (ref "R50") (pin "1") (pinfunction "1_1") (pintype "passive"))
      (node (ref "R7") (pin "1") (pinfunction "1_1") (pintype "passive"))
      (node (ref "R9") (pin "1") (pinfunction "1_1") (pintype "passive"))
      (node (ref "U$1") (pin "AC2") (pinfunction "1_AC2") (pintype "bidirectional"))
      (node (ref "U$1") (pin "AT1") (pinfunction "1_AT1") (pintype "bidirectional"))
      (node (ref "U$1") (pin "BC2") (pinfunction "1_BC2") (pintype "bidirectional"))
      (node (ref "U$1") (pin "BT1") (pinfunction "1_BT1") (pintype "bidirectional"))
    )
    (net (code "52") (name "Net-(AK2-P)") (class "Default")
      (node (ref "AK2") (pin "1") (pinfunction "P_1") (pintype "passive"))
      (node (ref "U$1") (pin "AK2") (pinfunction "1_AK2") (pintype "bidirectional"))
    )
    (net (code "53") (name "Net-(AS2-P)") (class "Default")
      (node (ref "AS2") (pin "1") (pinfunction "P_1") (pintype "passive"))
      (node (ref "U$1") (pin "AS2") (pinfunction "1_AS2") (pintype "bidirectional"))
    )
    (net (code "54") (name "Net-(BH2-P)") (class "Default")
      (node (ref "BH2") (pin "1") (pinfunction "P_1") (pintype "passive"))
      (node (ref "U$1") (pin "BH2") (pinfunction "1_BH2") (pintype "bidirectional"))
    )
    (net (code "55") (name "VCC") (class "Default")
      (node (ref "C1") (pin "1") (pinfunction "1_1") (pintype "passive"))
      (node (ref "C10") (pin "1") (pinfunction "1_1") (pintype "passive"))
      (node (ref "C11") (pin "1") (pinfunction "1_1") (pintype "passive"))
      (node (ref "C12") (pin "1") (pinfunction "1_1") (pintype "passive"))
      (node (ref "C13") (pin "1") (pinfunction "1_1") (pintype "passive"))
      (node (ref "C14") (pin "+") (pinfunction "+_+") (pintype "passive"))
      (node (ref "C15") (pin "+") (pinfunction "+_+") (pintype "passive"))
      (node (ref "C2") (pin "1") (pinfunction "1_1") (pintype "passive"))
      (node (ref "C3") (pin "1") (pinfunction "1_1") (pintype "passive"))
      (node (ref "C4") (pin "1") (pinfunction "1_1") (pintype "passive"))
      (node (ref "C5") (pin "1") (pinfunction "1_1") (pintype "passive"))
      (node (ref "C6") (pin "1") (pinfunction "1_1") (pintype "passive"))
      (node (ref "C7") (pin "1") (pinfunction "1_1") (pintype "passive"))
      (node (ref "C8") (pin "1") (pinfunction "1_1") (pintype "passive"))
      (node (ref "C9") (pin "1") (pinfunction "1_1") (pintype "passive"))
      (node (ref "R10") (pin "2") (pinfunction "2_2") (pintype "passive"))
      (node (ref "R12") (pin "2") (pinfunction "2_2") (pintype "passive"))
      (node (ref "R14") (pin "2") (pinfunction "2_2") (pintype "passive"))
      (node (ref "R16") (pin "2") (pinfunction "2_2") (pintype "passive"))
      (node (ref "R18") (pin "2") (pinfunction "2_2") (pintype "passive"))
      (node (ref "R2") (pin "2") (pinfunction "2_2") (pintype "passive"))
      (node (ref "R20") (pin "2") (pinfunction "2_2") (pintype "passive"))
      (node (ref "R22") (pin "2") (pinfunction "2_2") (pintype "passive"))
      (node (ref "R24") (pin "2") (pinfunction "2_2") (pintype "passive"))
      (node (ref "R25") (pin "2") (pinfunction "2_2") (pintype "passive"))
      (node (ref "R27") (pin "2") (pinfunction "2_2") (pintype "passive"))
      (node (ref "R29") (pin "2") (pinfunction "2_2") (pintype "passive"))
      (node (ref "R31") (pin "2") (pinfunction "2_2") (pintype "passive"))
      (node (ref "R33") (pin "2") (pinfunction "2_2") (pintype "passive"))
      (node (ref "R35") (pin "2") (pinfunction "2_2") (pintype "passive"))
      (node (ref "R37") (pin "2") (pinfunction "2_2") (pintype "passive"))
      (node (ref "R39") (pin "2") (pinfunction "2_2") (pintype "passive"))
      (node (ref "R4") (pin "2") (pinfunction "2_2") (pintype "passive"))
      (node (ref "R41") (pin "2") (pinfunction "2_2") (pintype "passive"))
      (node (ref "R43") (pin "2") (pinfunction "2_2") (pintype "passive"))
      (node (ref "R45") (pin "2") (pinfunction "2_2") (pintype "passive"))
      (node (ref "R47") (pin "2") (pinfunction "2_2") (pintype "passive"))
      (node (ref "R49") (pin "2") (pinfunction "2_2") (pintype "passive"))
      (node (ref "R6") (pin "2") (pinfunction "2_2") (pintype "passive"))
      (node (ref "R8") (pin "2") (pinfunction "2_2") (pintype "passive"))
      (node (ref "U$1") (pin "AA2") (pinfunction "1_AA2") (pintype "bidirectional"))
      (node (ref "U$1") (pin "BA2") (pinfunction "1_BA2") (pintype "bidirectional"))
    )
  )
)
